# WIFIBT_AP6398S.net
KiCad netlist of a schematic drawn in Altium Designer
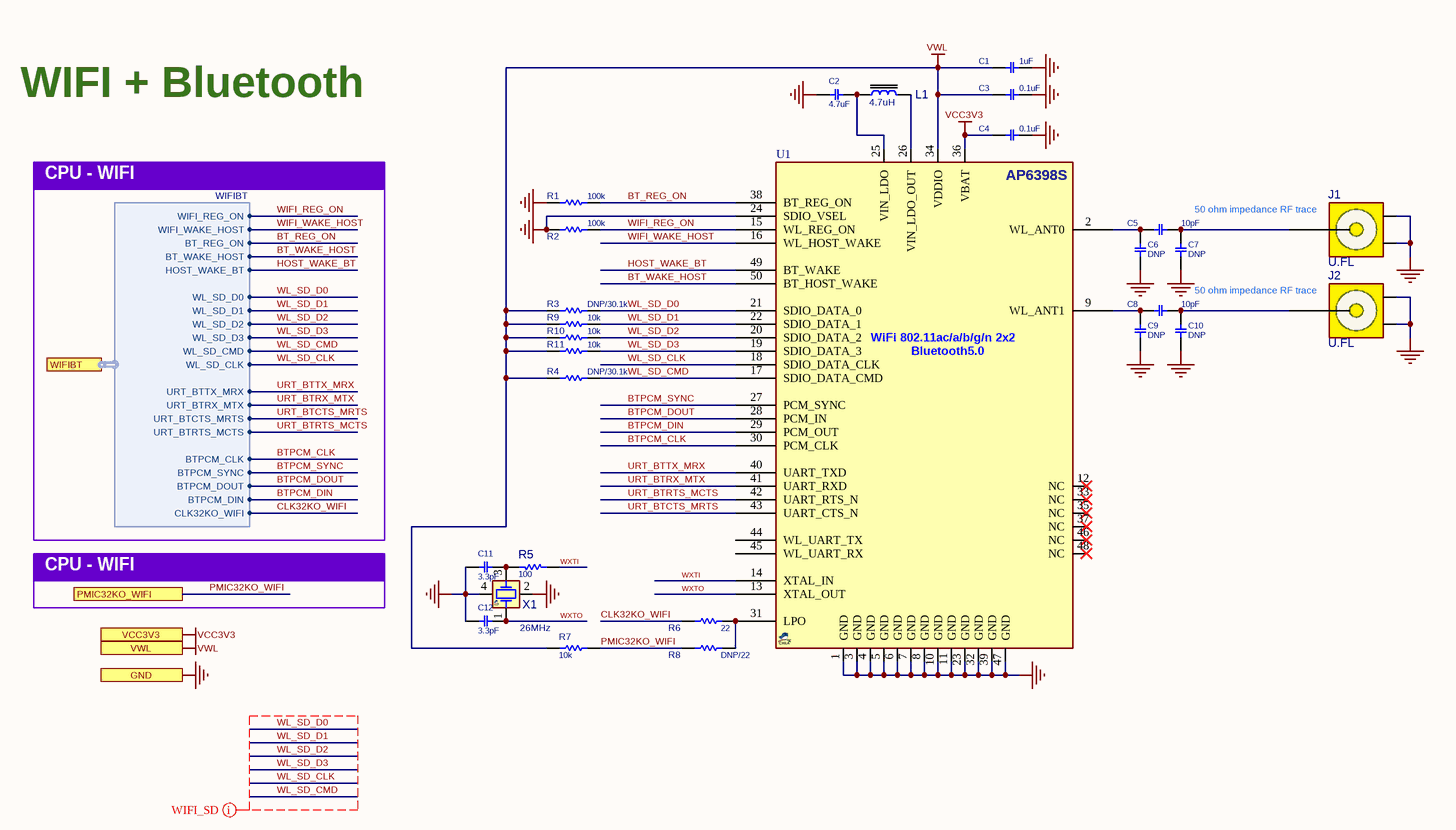
[diagram p0: WIFIBT_AP6398S.SchDoc]

(export (version "E")
  (design (tool "Eeschema 10.0.6"))
  (components
    (comp (ref "C1")
      (value "1uF")
      (footprint "C0402")
      (description "CAP, MLCC")
      (fields (field (name "MANF_P#") "CL05A105KO5NNND") (field (name "MANF") "Samsung"))
      (libsource (lib "passive_smd") (part "CAP_SMD_MLCC"))
    )
    (comp (ref "C2")
      (value "4.7uF")
      (footprint "C0402")
      (description "CAP, MLCC")
      (fields (field (name "MANF_P#") "LMK105BBJ475MVLF") (field (name "MANF") "Taiyo Yuden"))
      (libsource (lib "passive_smd") (part "CAP_SMD_MLCC"))
    )
    (comp (ref "C3")
      (value "0.1uF")
      (footprint "C0402")
      (description "CAP, MLCC")
      (fields (field (name "MANF_P#") "GRM155R61E104") (field (name "MANF") "Murata"))
      (libsource (lib "passive_smd") (part "CAP_SMD_MLCC"))
    )
    (comp (ref "C4")
      (value "0.1uF")
      (footprint "C0402")
      (description "CAP, MLCC")
      (fields (field (name "MANF_P#") "GRM155R61E104") (field (name "MANF") "Murata"))
      (libsource (lib "passive_smd") (part "CAP_SMD_MLCC"))
    )
    (comp (ref "C5")
      (value "10pF")
      (footprint "C0402")
      (description "CAP, MLCC")
      (fields (field (name "MANF_P#") "CC0402JRNPO9BN100") (field (name "MANF") "YAGEO"))
      (libsource (lib "passive_smd") (part "CAP_SMD_MLCC"))
    )
    (comp (ref "C6")
      (value "DNP")
      (footprint "C0402")
      (description "CAP, MLCC, 1nF, 50V, C0G, 10%, 0402")
      (libsource (lib "passive_smd") (part "CAP_SMD_MLCC"))
    )
    (comp (ref "C7")
      (value "DNP")
      (footprint "C0402")
      (description "CAP, MLCC, 1nF, 50V, C0G, 10%, 0402")
      (libsource (lib "passive_smd") (part "CAP_SMD_MLCC"))
    )
    (comp (ref "C8")
      (value "10pF")
      (footprint "C0402")
      (description "CAP, MLCC")
      (fields (field (name "MANF_P#") "CC0402JRNPO9BN100") (field (name "MANF") "YAGEO"))
      (libsource (lib "passive_smd") (part "CAP_SMD_MLCC"))
    )
    (comp (ref "C9")
      (value "DNP")
      (footprint "C0402")
      (description "CAP, MLCC, 1nF, 50V, C0G, 10%, 0402")
      (libsource (lib "passive_smd") (part "CAP_SMD_MLCC"))
    )
    (comp (ref "C10")
      (value "DNP")
      (footprint "C0402")
      (description "CAP, MLCC, 1nF, 50V, C0G, 10%, 0402")
      (libsource (lib "passive_smd") (part "CAP_SMD_MLCC"))
    )
    (comp (ref "C11")
      (value "3.3pF")
      (footprint "C0402")
      (description "CAP, MLCC")
      (fields (field (name "MANF_P#") "CC0402CRNPO9BN3R3") (field (name "MANF") "Yageo"))
      (libsource (lib "passive_smd") (part "CAP_SMD_MLCC"))
    )
    (comp (ref "C12")
      (value "3.3pF")
      (footprint "C0402")
      (description "CAP, MLCC")
      (fields (field (name "MANF_P#") "CC0402CRNPO9BN3R3") (field (name "MANF") "Yageo"))
      (libsource (lib "passive_smd") (part "CAP_SMD_MLCC"))
    )
    (comp (ref "J1")
      (value "U.FL")
      (footprint "UFL")
      (description "CONN, RF, U.FL, STRAIGHT, Ultra Miniature Coaxial")
      (fields
        (field (name "MANF_P#") "CONUFL001-SMD, U.FL-R-SMT-1(10), 128-0711-201")
        (field (name "MANF") "Linx, Hirose, Cinch")
      )
      (libsource (lib "conn_rf") (part "CONN_RF_UFL"))
    )
    (comp (ref "J2")
      (value "U.FL")
      (footprint "UFL")
      (description "CONN, RF, U.FL, STRAIGHT, Ultra Miniature Coaxial")
      (fields
        (field (name "MANF_P#") "CONUFL001-SMD, U.FL-R-SMT-1(10), 128-0711-201")
        (field (name "MANF") "Linx, Hirose, Cinch")
      )
      (libsource (lib "conn_rf") (part "CONN_RF_UFL"))
    )
    (comp (ref "L1")
      (value "4.7uH")
      (footprint "L_3")
      (description "INDUCTOR, POWER, SMD")
      (fields (field (name "MANF") "Bourns") (field (name "MANF_P#") "SRN3010-4R7M"))
      (libsource (lib "passive_smd") (part "INDPWR_SMD"))
    )
    (comp (ref "R1")
      (value "100k")
      (footprint "R0402")
      (description "RESISTOR, SMD")
      (libsource (lib "passive_res_smd") (part "RES_SMD"))
    )
    (comp (ref "R2")
      (value "100k")
      (footprint "R0402")
      (description "RESISTOR, SMD")
      (libsource (lib "passive_res_smd") (part "RES_SMD"))
    )
    (comp (ref "R3")
      (value "DNP/30.1k")
      (footprint "R0402")
      (description "RESISTOR, SMD")
      (libsource (lib "passive_res_smd") (part "RES_SMD"))
    )
    (comp (ref "R4")
      (value "DNP/30.1k")
      (footprint "R0402")
      (description "RESISTOR, SMD")
      (libsource (lib "passive_res_smd") (part "RES_SMD"))
    )
    (comp (ref "R5")
      (value "100")
      (footprint "R0402")
      (description "RESISTOR, SMD")
      (libsource (lib "passive_res_smd") (part "RES_SMD"))
    )
    (comp (ref "R6")
      (value "22")
      (footprint "R0402")
      (description "RESISTOR, SMD")
      (libsource (lib "passive_res_smd") (part "RES_SMD"))
    )
    (comp (ref "R7")
      (value "10k")
      (footprint "R0402")
      (description "RESISTOR, SMD")
      (libsource (lib "passive_res_smd") (part "RES_SMD"))
    )
    (comp (ref "R8")
      (value "DNP/22")
      (footprint "R0402")
      (description "RESISTOR, SMD")
      (libsource (lib "passive_res_smd") (part "RES_SMD"))
    )
    (comp (ref "R9")
      (value "10k")
      (footprint "R0402")
      (description "RESISTOR, SMD")
      (libsource (lib "passive_res_smd") (part "RES_SMD"))
    )
    (comp (ref "R10")
      (value "10k")
      (footprint "R0402")
      (description "RESISTOR, SMD")
      (libsource (lib "passive_res_smd") (part "RES_SMD"))
    )
    (comp (ref "R11")
      (value "10k")
      (footprint "R0402")
      (description "RESISTOR, SMD")
      (libsource (lib "passive_res_smd") (part "RES_SMD"))
    )
    (comp (ref "U1")
      (value "AP6398S")
      (footprint "AP6398S_50")
      (description "WiFi with Bluetooth 5.0,")
      (fields (field (name "MANF") "AMPAK"))
      (libsource (lib "module_wifi") (part "AP6398S"))
    )
    (comp (ref "X1")
      (value "26MHz")
      (footprint "XTL_4_2016")
      (description "CRYSTAL")
      (fields (field (name "MANF") "Murata") (field (name "MANF_P#") "XRCGB26M000F2P00R0"))
      (libsource (lib "crystal") (part "XTL_4_40MHz_3225F"))
    )
  )
  (nets
    (net (code "2") (name "/BTPCM_CLK") (class "Default")
      (node (ref "U1") (pin "30") (pinfunction "PCM_CLK_30") (pintype "power_in"))
    )
    (net (code "3") (name "/BTPCM_DIN") (class "Default")
      (node (ref "U1") (pin "29") (pinfunction "PCM_OUT_29") (pintype "power_in"))
    )
    (net (code "4") (name "/BTPCM_DOUT") (class "Default")
      (node (ref "U1") (pin "28") (pinfunction "PCM_IN_28") (pintype "power_in"))
    )
    (net (code "5") (name "/BTPCM_SYNC") (class "Default")
      (node (ref "U1") (pin "27") (pinfunction "PCM_SYNC_27") (pintype "power_in"))
    )
    (net (code "6") (name "/BT_REG_ON") (class "Default")
      (node (ref "R1") (pin "1") (pinfunction "1_1") (pintype "passive"))
      (node (ref "U1") (pin "38") (pinfunction "BT_REG_ON_38") (pintype "power_in"))
    )
    (net (code "7") (name "/BT_WAKE_HOST") (class "Default")
      (node (ref "U1") (pin "50") (pinfunction "BT_HOST_WAKE_50") (pintype "power_in"))
    )
    (net (code "8") (name "/CLK32KO_WIFI") (class "Default")
      (node (ref "R6") (pin "2") (pinfunction "2_2") (pintype "passive"))
    )
    (net (code "9") (name "/HOST_WAKE_BT") (class "Default")
      (node (ref "U1") (pin "49") (pinfunction "BT_WAKE_49") (pintype "power_in"))
    )
    (net (code "10") (name "/PMIC32KO_WIFI") (class "Default")
      (node (ref "R7") (pin "2") (pinfunction "2_2") (pintype "passive"))
      (node (ref "R8") (pin "2") (pinfunction "2_2") (pintype "passive"))
    )
    (net (code "11") (name "/URT_BTCTS_MRTS") (class "Default")
      (node (ref "U1") (pin "43") (pinfunction "UART_CTS_N_43") (pintype "power_in"))
    )
    (net (code "12") (name "/URT_BTRTS_MCTS") (class "Default")
      (node (ref "U1") (pin "42") (pinfunction "UART_RTS_N_42") (pintype "power_in"))
    )
    (net (code "13") (name "/URT_BTRX_MTX") (class "Default")
      (node (ref "U1") (pin "41") (pinfunction "UART_RXD_41") (pintype "power_in"))
    )
    (net (code "14") (name "/URT_BTTX_MRX") (class "Default")
      (node (ref "U1") (pin "40") (pinfunction "UART_TXD_40") (pintype "power_in"))
    )
    (net (code "15") (name "/WIFI_REG_ON") (class "Default")
      (node (ref "R2") (pin "1") (pinfunction "1_1") (pintype "passive"))
      (node (ref "U1") (pin "15") (pinfunction "WL_REG_ON_15") (pintype "power_in"))
    )
    (net (code "16") (name "/WIFI_WAKE_HOST") (class "Default")
      (node (ref "U1") (pin "16") (pinfunction "WL_HOST_WAKE_16") (pintype "power_in"))
    )
    (net (code "17") (name "/WL_SD_CLK") (class "Default")
      (node (ref "U1") (pin "18") (pinfunction "SDIO_DATA_CLK_18") (pintype "power_in"))
    )
    (net (code "18") (name "/WL_SD_CMD") (class "Default")
      (node (ref "R4") (pin "1") (pinfunction "1_1") (pintype "passive"))
      (node (ref "U1") (pin "17") (pinfunction "SDIO_DATA_CMD_17") (pintype "power_in"))
    )
    (net (code "19") (name "/WL_SD_D0") (class "Default")
      (node (ref "R3") (pin "1") (pinfunction "1_1") (pintype "passive"))
      (node (ref "U1") (pin "21") (pinfunction "SDIO_DATA_0_21") (pintype "power_in"))
    )
    (net (code "20") (name "/WL_SD_D1") (class "Default")
      (node (ref "R9") (pin "1") (pinfunction "1_1") (pintype "passive"))
      (node (ref "U1") (pin "22") (pinfunction "SDIO_DATA_1_22") (pintype "power_in"))
    )
    (net (code "21") (name "/WL_SD_D2") (class "Default")
      (node (ref "R10") (pin "1") (pinfunction "1_1") (pintype "passive"))
      (node (ref "U1") (pin "20") (pinfunction "SDIO_DATA_2_20") (pintype "power_in"))
    )
    (net (code "22") (name "/WL_SD_D3") (class "Default")
      (node (ref "R11") (pin "1") (pinfunction "1_1") (pintype "passive"))
      (node (ref "U1") (pin "19") (pinfunction "SDIO_DATA_3_19") (pintype "power_in"))
    )
    (net (code "23") (name "/WXTI") (class "Default")
      (node (ref "R5") (pin "2") (pinfunction "2_2") (pintype "passive"))
      (node (ref "U1") (pin "14") (pinfunction "XTAL_IN_14") (pintype "power_in"))
    )
    (net (code "24") (name "/WXTO") (class "Default")
      (node (ref "C12") (pin "1") (pinfunction "1_1") (pintype "passive"))
      (node (ref "U1") (pin "13") (pinfunction "XTAL_OUT_13") (pintype "power_in"))
      (node (ref "X1") (pin "1") (pinfunction "XA_1") (pintype "passive"))
    )
    (net (code "26") (name "GND") (class "Default")
      (node (ref "C1") (pin "1") (pinfunction "1_1") (pintype "passive"))
      (node (ref "C10") (pin "2") (pinfunction "2_2") (pintype "passive"))
      (node (ref "C11") (pin "2") (pinfunction "2_2") (pintype "passive"))
      (node (ref "C12") (pin "2") (pinfunction "2_2") (pintype "passive"))
      (node (ref "C2") (pin "2") (pinfunction "2_2") (pintype "passive"))
      (node (ref "C3") (pin "1") (pinfunction "1_1") (pintype "passive"))
      (node (ref "C4") (pin "1") (pinfunction "1_1") (pintype "passive"))
      (node (ref "C6") (pin "2") (pinfunction "2_2") (pintype "passive"))
      (node (ref "C7") (pin "2") (pinfunction "2_2") (pintype "passive"))
      (node (ref "C9") (pin "2") (pinfunction "2_2") (pintype "passive"))
      (node (ref "J1") (pin "2") (pinfunction "G1_2") (pintype "passive"))
      (node (ref "J1") (pin "3") (pinfunction "G2_3") (pintype "passive"))
      (node (ref "J2") (pin "2") (pinfunction "G1_2") (pintype "passive"))
      (node (ref "J2") (pin "3") (pinfunction "G2_3") (pintype "passive"))
      (node (ref "R1") (pin "2") (pinfunction "2_2") (pintype "passive"))
      (node (ref "R2") (pin "2") (pinfunction "2_2") (pintype "passive"))
      (node (ref "U1") (pin "1") (pinfunction "GND_1") (pintype "power_in"))
      (node (ref "U1") (pin "10") (pinfunction "GND_10") (pintype "power_in"))
      (node (ref "U1") (pin "11") (pinfunction "GND_11") (pintype "power_in"))
      (node (ref "U1") (pin "23") (pinfunction "GND_23") (pintype "power_in"))
      (node (ref "U1") (pin "24") (pinfunction "SDIO_VSEL_24") (pintype "power_in"))
      (node (ref "U1") (pin "3") (pinfunction "GND_3") (pintype "power_in"))
      (node (ref "U1") (pin "32") (pinfunction "GND_32") (pintype "power_in"))
      (node (ref "U1") (pin "39") (pinfunction "GND_39") (pintype "power_in"))
      (node (ref "U1") (pin "4") (pinfunction "GND_4") (pintype "power_in"))
      (node (ref "U1") (pin "47") (pinfunction "GND_47") (pintype "power_in"))
      (node (ref "U1") (pin "5") (pinfunction "GND_5") (pintype "power_in"))
      (node (ref "U1") (pin "6") (pinfunction "GND_6") (pintype "power_in"))
      (node (ref "U1") (pin "7") (pinfunction "GND_7") (pintype "power_in"))
      (node (ref "U1") (pin "8") (pinfunction "GND_8") (pintype "power_in"))
      (node (ref "X1") (pin "2") (pinfunction "GND1_2") (pintype "passive"))
      (node (ref "X1") (pin "4") (pinfunction "GND2_4") (pintype "passive"))
    )
    (net (code "27") (name "Net-(J1-SIG)") (class "Default")
      (node (ref "C5") (pin "1") (pinfunction "1_1") (pintype "passive"))
      (node (ref "C7") (pin "1") (pinfunction "1_1") (pintype "passive"))
      (node (ref "J1") (pin "1") (pinfunction "SIG_1") (pintype "passive"))
    )
    (net (code "28") (name "Net-(J2-SIG)") (class "Default")
      (node (ref "C10") (pin "1") (pinfunction "1_1") (pintype "passive"))
      (node (ref "C8") (pin "1") (pinfunction "1_1") (pintype "passive"))
      (node (ref "J2") (pin "1") (pinfunction "SIG_1") (pintype "passive"))
    )
    (net (code "29") (name "Net-(U1-LPO)") (class "Default")
      (node (ref "R6") (pin "1") (pinfunction "1_1") (pintype "passive"))
      (node (ref "R8") (pin "1") (pinfunction "1_1") (pintype "passive"))
      (node (ref "U1") (pin "31") (pinfunction "LPO_31") (pintype "power_in"))
    )
    (net (code "30") (name "Net-(U1-VIN_LDO)") (class "Default")
      (node (ref "C2") (pin "1") (pinfunction "1_1") (pintype "passive"))
      (node (ref "L1") (pin "1") (pinfunction "1_1") (pintype "passive"))
      (node (ref "U1") (pin "25") (pinfunction "VIN_LDO_25") (pintype "power_in"))
    )
    (net (code "31") (name "Net-(U1-VIN_LDO_OUT)") (class "Default")
      (node (ref "L1") (pin "2") (pinfunction "2_2") (pintype "passive"))
      (node (ref "U1") (pin "26") (pinfunction "VIN_LDO_OUT_26") (pintype "power_in"))
    )
    (net (code "32") (name "Net-(U1-WL_ANT0)") (class "Default")
      (node (ref "C5") (pin "2") (pinfunction "2_2") (pintype "passive"))
      (node (ref "C6") (pin "1") (pinfunction "1_1") (pintype "passive"))
      (node (ref "U1") (pin "2") (pinfunction "WL_ANT0_2") (pintype "power_in"))
    )
    (net (code "33") (name "Net-(U1-WL_ANT1)") (class "Default")
      (node (ref "C8") (pin "2") (pinfunction "2_2") (pintype "passive"))
      (node (ref "C9") (pin "1") (pinfunction "1_1") (pintype "passive"))
      (node (ref "U1") (pin "9") (pinfunction "WL_ANT1_9") (pintype "power_in"))
    )
    (net (code "34") (name "Net-(X1-XB)") (class "Default")
      (node (ref "C11") (pin "1") (pinfunction "1_1") (pintype "passive"))
      (node (ref "R5") (pin "1") (pinfunction "1_1") (pintype "passive"))
      (node (ref "X1") (pin "3") (pinfunction "XB_3") (pintype "passive"))
    )
    (net (code "35") (name "VCC3V3") (class "Default")
      (node (ref "C4") (pin "2") (pinfunction "2_2") (pintype "passive"))
      (node (ref "U1") (pin "36") (pinfunction "VBAT_36") (pintype "power_in"))
    )
    (net (code "36") (name "VWL") (class "Default")
      (node (ref "C1") (pin "2") (pinfunction "2_2") (pintype "passive"))
      (node (ref "C3") (pin "2") (pinfunction "2_2") (pintype "passive"))
      (node (ref "R10") (pin "2") (pinfunction "2_2") (pintype "passive"))
      (node (ref "R11") (pin "2") (pinfunction "2_2") (pintype "passive"))
      (node (ref "R3") (pin "2") (pinfunction "2_2") (pintype "passive"))
      (node (ref "R4") (pin "2") (pinfunction "2_2") (pintype "passive"))
      (node (ref "R7") (pin "1") (pinfunction "1_1") (pintype "passive"))
      (node (ref "R9") (pin "2") (pinfunction "2_2") (pintype "passive"))
      (node (ref "U1") (pin "34") (pinfunction "VDDIO_34") (pintype "power_in"))
    )
    (net (code "37") (name "unconnected-(U1-NC-Pad12)") (class "Default")
      (node (ref "U1") (pin "12") (pinfunction "NC_12") (pintype "power_in+no_connect"))
    )
    (net (code "38") (name "unconnected-(U1-NC-Pad33)") (class "Default")
      (node (ref "U1") (pin "33") (pinfunction "NC_33") (pintype "power_in+no_connect"))
    )
    (net (code "39") (name "unconnected-(U1-NC-Pad35)") (class "Default")
      (node (ref "U1") (pin "35") (pinfunction "NC_35") (pintype "power_in+no_connect"))
    )
    (net (code "40") (name "unconnected-(U1-NC-Pad37)") (class "Default")
      (node (ref "U1") (pin "37") (pinfunction "NC_37") (pintype "power_in+no_connect"))
    )
    (net (code "41") (name "unconnected-(U1-NC-Pad46)") (class "Default")
      (node (ref "U1") (pin "46") (pinfunction "NC_46") (pintype "power_in+no_connect"))
    )
    (net (code "42") (name "unconnected-(U1-NC-Pad48)") (class "Default")
      (node (ref "U1") (pin "48") (pinfunction "NC_48") (pintype "power_in+no_connect"))
    )
    (net (code "43") (name "unconnected-(U1-WL_UART_RX-Pad45)") (class "Default")
      (node (ref "U1") (pin "45") (pinfunction "WL_UART_RX_45") (pintype "power_in"))
    )
    (net (code "44") (name "unconnected-(U1-WL_UART_TX-Pad44)") (class "Default")
      (node (ref "U1") (pin "44") (pinfunction "WL_UART_TX_44") (pintype "power_in"))
    )
  )
)
